# MB.net
KiCad netlist of a schematic drawn in Altium Designer
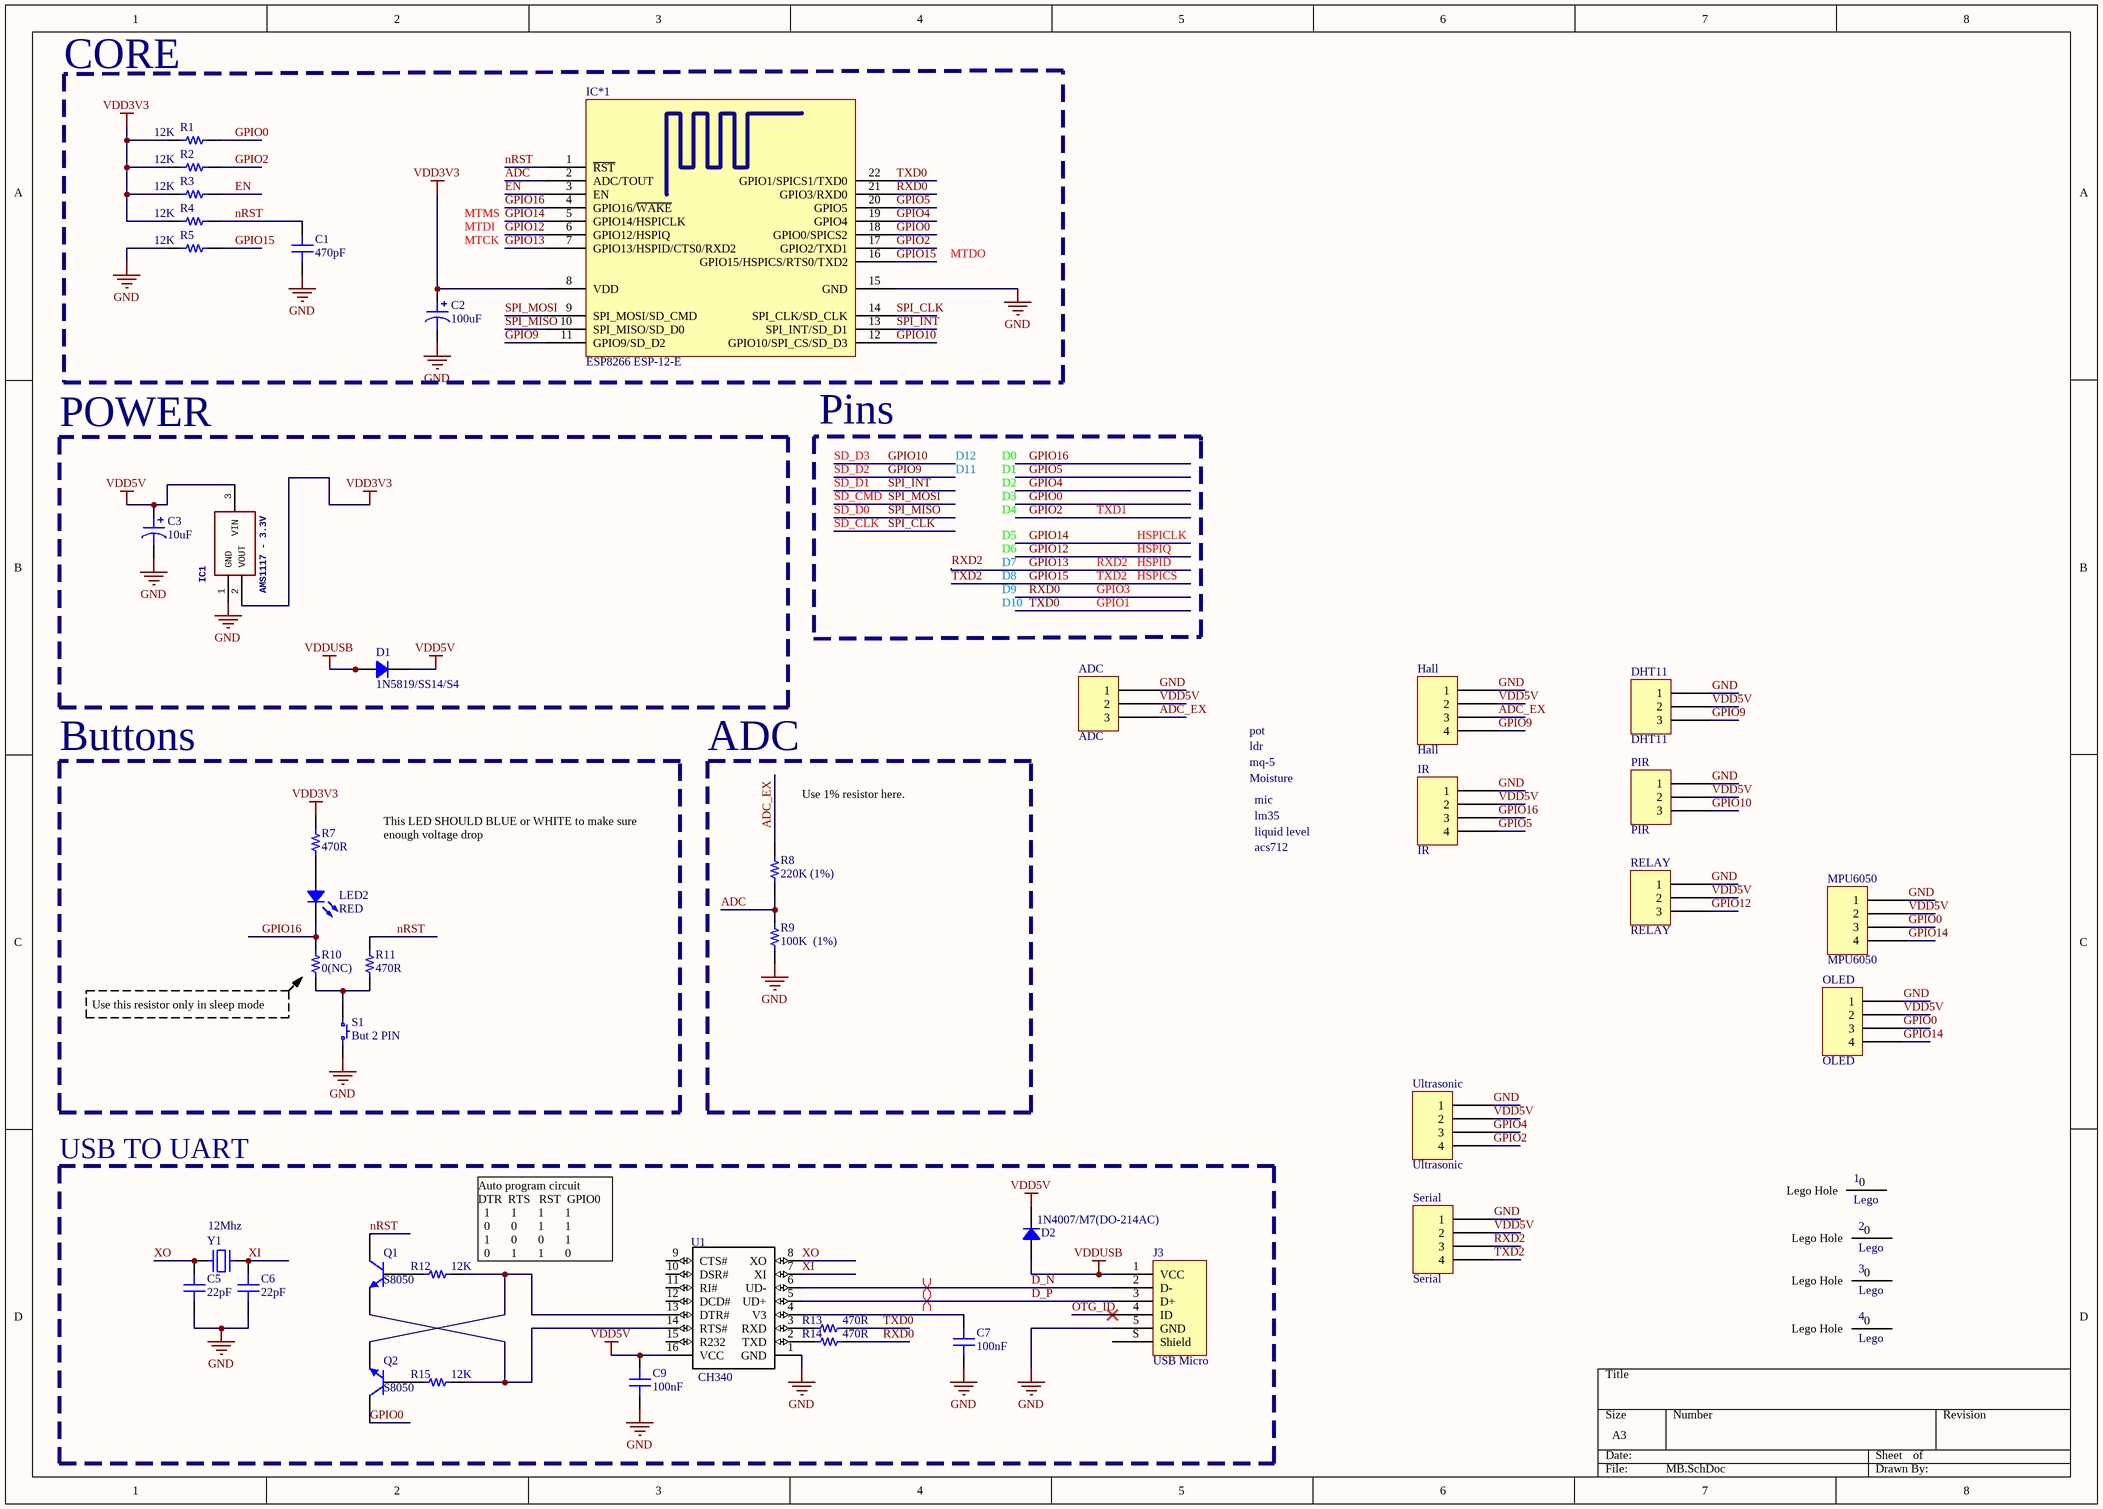
[diagram p0: MB.SchDoc]

(export (version "E")
  (design (tool "Eeschema 10.0.6"))
  (components
    (comp (ref "1") (value "Lego") (footprint "Lego Hole") (libsource (lib "Connectors") (part "Lego")))
    (comp (ref "2") (value "Lego") (footprint "Lego Hole") (libsource (lib "Connectors") (part "Lego")))
    (comp (ref "3") (value "Lego") (footprint "Lego Hole") (libsource (lib "Connectors") (part "Lego")))
    (comp (ref "4") (value "Lego") (footprint "Lego Hole") (libsource (lib "Connectors") (part "Lego")))
    (comp (ref "ADC")
      (value "ADC")
      (footprint "JST XH B3B-XH-A")
      (libsource (lib "Connectors") (part "3 Pin"))
    )
    (comp (ref "C1")
      (value "470pF")
      (footprint "CAP 1206/3216")
      (description "SMT Capacitor")
      (libsource (lib "Cap_Res") (part "Capacitor"))
    )
    (comp (ref "C2")
      (value "100uF")
      (footprint "CAP ALUM 5MM")
      (description "SMT Polarised Capacitor")
      (libsource (lib "Cap_Res") (part "Polarised Capacitor"))
    )
    (comp (ref "C3")
      (value "10uF")
      (footprint "CAP ALUM 5MM")
      (description "SMT Polarised Capacitor")
      (libsource (lib "Cap_Res") (part "Polarised Capacitor"))
    )
    (comp (ref "C5")
      (value "22pF")
      (footprint "CAP 1206/3216")
      (description "SMT Capacitor")
      (libsource (lib "Cap_Res") (part "Capacitor"))
    )
    (comp (ref "C6")
      (value "22pF")
      (footprint "CAP 1206/3216")
      (description "SMT Capacitor")
      (libsource (lib "Cap_Res") (part "Capacitor"))
    )
    (comp (ref "C7")
      (value "100nF")
      (footprint "CAP 1206/3216")
      (description "SMT Capacitor")
      (libsource (lib "Cap_Res") (part "Capacitor"))
    )
    (comp (ref "C9")
      (value "100nF")
      (footprint "CAP 1206/3216")
      (description "SMT Capacitor")
      (libsource (lib "Cap_Res") (part "Capacitor"))
    )
    (comp (ref "D1")
      (value "1N5819/SS14/S4")
      (footprint "DO214AC SMA")
      (description "Rectifier Diode")
      (libsource (lib "Cap_Res") (part "Diode"))
    )
    (comp (ref "D2")
      (value "1N4007/M7(DO-214AC)")
      (footprint "DO214AC SMA")
      (description "Rectifier Diode")
      (libsource (lib "Cap_Res") (part "Diode"))
    )
    (comp (ref "DHT11")
      (value "DHT11")
      (footprint "JST XH B3B-XH-A")
      (libsource (lib "Connectors") (part "3 Pin"))
    )
    (comp (ref "Hall")
      (value "Hall")
      (footprint "JST XH B4B-XH-A")
      (libsource (lib "Connectors") (part "4 Pin"))
    )
    (comp (ref "IC*1")
      (value "ESP8266 ESP-12-E")
      (footprint "ESP8266 ESP-12-E")
      (libsource (lib "ESP8266") (part "ESP8266 ESP-12-E"))
    )
    (comp (ref "IC1")
      (value "AMS1117 - 3.3V")
      (footprint "AMS1117")
      (fields (field (name "MANUFACTURER_PART_NUMBER") "ams1117-3.3v"))
      (libsource (lib "Other") (part "AMS1117"))
    )
    (comp (ref "IR") (value "IR") (footprint "JST XH B4B-XH-A") (libsource (lib "Connectors") (part "4 Pin")))
    (comp (ref "J3")
      (value "USB Micro")
      (footprint "FCI USB 10118193-0001LF")
      (libsource (lib "Connectors") (part "USB 2.0 Type B Micro"))
    )
    (comp (ref "LED2")
      (value "RED")
      (footprint "LED 1206/3216 BLUE")
      (description "Chip LED")
      (libsource (lib "Cap_Res") (part "LED"))
    )
    (comp (ref "MPU6050")
      (value "MPU6050")
      (footprint "JST XH B4B-XH-A")
      (libsource (lib "Connectors") (part "4 Pin"))
    )
    (comp (ref "OLED")
      (value "OLED")
      (footprint "JST XH B4B-XH-A")
      (libsource (lib "Connectors") (part "4 Pin"))
    )
    (comp (ref "PIR")
      (value "PIR")
      (footprint "JST XH B3B-XH-A")
      (libsource (lib "Connectors") (part "3 Pin"))
    )
    (comp (ref "Q1")
      (value "S8050")
      (footprint "SOT23")
      (description "NPN")
      (fields (field (name "E-MAIL") "picpars@gmail.com"))
      (libsource (lib "Other") (part "2N2222"))
    )
    (comp (ref "Q2")
      (value "S8050")
      (footprint "SOT23")
      (description "NPN")
      (fields (field (name "E-MAIL") "picpars@gmail.com"))
      (libsource (lib "Other") (part "2N2222"))
    )
    (comp (ref "R1")
      (value "12K")
      (footprint "RES 1206/3216")
      (description "SMT Resistor")
      (libsource (lib "Cap_Res") (part "Resistor"))
    )
    (comp (ref "R2")
      (value "12K")
      (footprint "RES 1206/3216")
      (description "SMT Resistor")
      (libsource (lib "Cap_Res") (part "Resistor"))
    )
    (comp (ref "R3")
      (value "12K")
      (footprint "RES 1206/3216")
      (description "SMT Resistor")
      (libsource (lib "Cap_Res") (part "Resistor"))
    )
    (comp (ref "R4")
      (value "12K")
      (footprint "RES 1206/3216")
      (description "SMT Resistor")
      (libsource (lib "Cap_Res") (part "Resistor"))
    )
    (comp (ref "R5")
      (value "12K")
      (footprint "RES 1206/3216")
      (description "SMT Resistor")
      (libsource (lib "Cap_Res") (part "Resistor"))
    )
    (comp (ref "R7")
      (value "470R")
      (footprint "RES 1206/3216")
      (description "SMT Resistor")
      (libsource (lib "Cap_Res") (part "Resistor"))
    )
    (comp (ref "R8")
      (value "220K (1%)")
      (footprint "RES 1206/3216")
      (description "SMT Resistor")
      (libsource (lib "Cap_Res") (part "Resistor"))
    )
    (comp (ref "R9")
      (value "100K  (1%)")
      (footprint "RES 1206/3216")
      (description "SMT Resistor")
      (libsource (lib "Cap_Res") (part "Resistor"))
    )
    (comp (ref "R10")
      (value "0(NC)")
      (footprint "RES 1206/3216")
      (description "SMT Resistor")
      (libsource (lib "Cap_Res") (part "Resistor"))
    )
    (comp (ref "R11")
      (value "470R")
      (footprint "RES 1206/3216")
      (description "SMT Resistor")
      (libsource (lib "Cap_Res") (part "Resistor"))
    )
    (comp (ref "R12")
      (value "12K")
      (footprint "RES 1206/3216")
      (description "SMT Resistor")
      (libsource (lib "Cap_Res") (part "Resistor"))
    )
    (comp (ref "R13")
      (value "470R")
      (footprint "RES 1206/3216")
      (description "SMT Resistor")
      (libsource (lib "Cap_Res") (part "Resistor"))
    )
    (comp (ref "R14")
      (value "470R")
      (footprint "RES 1206/3216")
      (description "SMT Resistor")
      (libsource (lib "Cap_Res") (part "Resistor"))
    )
    (comp (ref "R15")
      (value "12K")
      (footprint "RES 1206/3216")
      (description "SMT Resistor")
      (libsource (lib "Cap_Res") (part "Resistor"))
    )
    (comp (ref "RELAY")
      (value "RELAY")
      (footprint "JST XH B3B-XH-A")
      (libsource (lib "Connectors") (part "3 Pin"))
    )
    (comp (ref "S1")
      (value "But 2 PIN")
      (footprint "TE FSMSMTR")
      (libsource (lib "Other") (part "But 2 PIN"))
    )
    (comp (ref "Serial")
      (value "Serial")
      (footprint "JST XH B4B-XH-A")
      (libsource (lib "Connectors") (part "4 Pin"))
    )
    (comp (ref "U1")
      (value "CH340")
      (footprint "SO16")
      (fields (field (name "MF") "Eaton / Cutler Hammer"))
      (libsource (lib "Other") (part "CH340"))
    )
    (comp (ref "Ultrasonic")
      (value "Ultrasonic")
      (footprint "JST XH B4B-XH-A")
      (libsource (lib "Connectors") (part "4 Pin"))
    )
    (comp (ref "Y1")
      (value "12Mhz")
      (footprint "xtal")
      (description "SMT Crystal")
      (libsource (lib "Other") (part "xtal"))
    )
  )
  (nets
    (net (code "1") (name "/ADC") (class "Default")
      (node (ref "IC*1") (pin "2") (pinfunction "ADC/TOUT_2") (pintype "passive"))
      (node (ref "R8") (pin "2") (pinfunction "2_2") (pintype "passive"))
      (node (ref "R9") (pin "1") (pinfunction "1_1") (pintype "passive"))
    )
    (net (code "2") (name "/ADC_EX") (class "Default")
      (node (ref "ADC") (pin "3") (pinfunction "3_3") (pintype "passive"))
      (node (ref "Hall") (pin "3") (pinfunction "3_3") (pintype "passive"))
      (node (ref "R8") (pin "1") (pinfunction "1_1") (pintype "passive"))
    )
    (net (code "3") (name "/D_N") (class "Default")
      (node (ref "J3") (pin "2") (pinfunction "D-_2") (pintype "passive"))
      (node (ref "U1") (pin "6") (pinfunction "UD-_6") (pintype "bidirectional"))
    )
    (net (code "4") (name "/D_P") (class "Default")
      (node (ref "J3") (pin "3") (pinfunction "D+_3") (pintype "passive"))
      (node (ref "U1") (pin "5") (pinfunction "UD+_5") (pintype "bidirectional"))
    )
    (net (code "5") (name "/EN") (class "Default")
      (node (ref "IC*1") (pin "3") (pinfunction "EN_3") (pintype "passive"))
      (node (ref "R3") (pin "1") (pinfunction "1_1") (pintype "passive"))
    )
    (net (code "6") (name "/GPIO0") (class "Default")
      (node (ref "IC*1") (pin "18") (pinfunction "GPIO0/SPICS2_18") (pintype "passive"))
      (node (ref "MPU6050") (pin "3") (pinfunction "3_3") (pintype "passive"))
      (node (ref "OLED") (pin "3") (pinfunction "3_3") (pintype "passive"))
      (node (ref "Q2") (pin "C") (pinfunction "C_C") (pintype "passive"))
      (node (ref "R1") (pin "1") (pinfunction "1_1") (pintype "passive"))
    )
    (net (code "7") (name "/GPIO2") (class "Default")
      (node (ref "IC*1") (pin "17") (pinfunction "GPIO2/TXD1_17") (pintype "passive"))
      (node (ref "R2") (pin "1") (pinfunction "1_1") (pintype "passive"))
      (node (ref "Ultrasonic") (pin "4") (pinfunction "4_4") (pintype "passive"))
    )
    (net (code "8") (name "/GPIO4") (class "Default")
      (node (ref "IC*1") (pin "19") (pinfunction "GPIO4_19") (pintype "passive"))
      (node (ref "Ultrasonic") (pin "3") (pinfunction "3_3") (pintype "passive"))
    )
    (net (code "9") (name "/GPIO5") (class "Default")
      (node (ref "IC*1") (pin "20") (pinfunction "GPIO5_20") (pintype "passive"))
      (node (ref "IR") (pin "4") (pinfunction "4_4") (pintype "passive"))
    )
    (net (code "10") (name "/GPIO9") (class "Default")
      (node (ref "DHT11") (pin "3") (pinfunction "3_3") (pintype "passive"))
      (node (ref "Hall") (pin "4") (pinfunction "4_4") (pintype "passive"))
      (node (ref "IC*1") (pin "11") (pinfunction "GPIO9/SD_D2_11") (pintype "passive"))
    )
    (net (code "11") (name "/GPIO10") (class "Default")
      (node (ref "IC*1") (pin "12") (pinfunction "GPIO10/SPI_CS/SD_D3_12") (pintype "passive"))
      (node (ref "PIR") (pin "3") (pinfunction "3_3") (pintype "passive"))
    )
    (net (code "12") (name "/GPIO12") (class "Default")
      (node (ref "IC*1") (pin "6") (pinfunction "GPIO12/HSPIQ_6") (pintype "passive"))
      (node (ref "RELAY") (pin "3") (pinfunction "3_3") (pintype "passive"))
    )
    (net (code "13") (name "/GPIO13") (class "Default")
      (node (ref "IC*1") (pin "7") (pinfunction "GPIO13/HSPID/CTS0/RXD2_7") (pintype "passive"))
      (node (ref "Serial") (pin "3") (pinfunction "3_3") (pintype "passive"))
    )
    (net (code "14") (name "/GPIO14") (class "Default")
      (node (ref "IC*1") (pin "5") (pinfunction "GPIO14/HSPICLK_5") (pintype "passive"))
      (node (ref "MPU6050") (pin "4") (pinfunction "4_4") (pintype "passive"))
      (node (ref "OLED") (pin "4") (pinfunction "4_4") (pintype "passive"))
    )
    (net (code "15") (name "/GPIO15") (class "Default")
      (node (ref "IC*1") (pin "16") (pinfunction "GPIO15/HSPICS/RTS0/TXD2_16") (pintype "passive"))
      (node (ref "R5") (pin "1") (pinfunction "1_1") (pintype "passive"))
      (node (ref "Serial") (pin "4") (pinfunction "4_4") (pintype "passive"))
    )
    (net (code "16") (name "/GPIO16") (class "Default")
      (node (ref "IC*1") (pin "4") (pinfunction "GPIO16/~{WAKE}_4") (pintype "passive"))
      (node (ref "IR") (pin "3") (pinfunction "3_3") (pintype "passive"))
      (node (ref "LED2") (pin "2") (pinfunction "2_2") (pintype "passive"))
      (node (ref "R10") (pin "1") (pinfunction "1_1") (pintype "passive"))
    )
    (net (code "17") (name "/OTG_ID") (class "Default")
      (node (ref "J3") (pin "4") (pinfunction "ID_4") (pintype "passive+no_connect"))
    )
    (net (code "18") (name "/RXD0") (class "Default")
      (node (ref "IC*1") (pin "21") (pinfunction "GPIO3/RXD0_21") (pintype "passive"))
      (node (ref "R14") (pin "2") (pinfunction "2_2") (pintype "passive"))
    )
    (net (code "19") (name "/SPI_CLK") (class "Default")
      (node (ref "IC*1") (pin "14") (pinfunction "SPI_CLK/SD_CLK_14") (pintype "passive"))
    )
    (net (code "20") (name "/SPI_INT") (class "Default")
      (node (ref "IC*1") (pin "13") (pinfunction "SPI_INT/SD_D1_13") (pintype "passive"))
    )
    (net (code "21") (name "/SPI_MISO") (class "Default")
      (node (ref "IC*1") (pin "10") (pinfunction "SPI_MISO/SD_D0_10") (pintype "passive"))
    )
    (net (code "22") (name "/SPI_MOSI") (class "Default")
      (node (ref "IC*1") (pin "9") (pinfunction "SPI_MOSI/SD_CMD_9") (pintype "passive"))
    )
    (net (code "23") (name "/TXD0") (class "Default")
      (node (ref "IC*1") (pin "22") (pinfunction "GPIO1/SPICS1/TXD0_22") (pintype "passive"))
      (node (ref "R13") (pin "2") (pinfunction "2_2") (pintype "passive"))
    )
    (net (code "24") (name "/XI") (class "Default")
      (node (ref "C6") (pin "2") (pinfunction "2_2") (pintype "passive"))
      (node (ref "U1") (pin "7") (pinfunction "XI_7") (pintype "bidirectional"))
      (node (ref "Y1") (pin "2") (pinfunction "2_2") (pintype "passive"))
    )
    (net (code "25") (name "/XO") (class "Default")
      (node (ref "C5") (pin "2") (pinfunction "2_2") (pintype "passive"))
      (node (ref "U1") (pin "8") (pinfunction "XO_8") (pintype "bidirectional"))
      (node (ref "Y1") (pin "1") (pinfunction "1_1") (pintype "passive"))
    )
    (net (code "26") (name "/nRST") (class "Default")
      (node (ref "C1") (pin "2") (pinfunction "2_2") (pintype "passive"))
      (node (ref "IC*1") (pin "1") (pinfunction "~{RST}_1") (pintype "passive"))
      (node (ref "Q1") (pin "C") (pinfunction "C_C") (pintype "passive"))
      (node (ref "R11") (pin "1") (pinfunction "1_1") (pintype "passive"))
      (node (ref "R4") (pin "1") (pinfunction "1_1") (pintype "passive"))
    )
    (net (code "27") (name "GND") (class "Default")
      (node (ref "ADC") (pin "1") (pinfunction "1_1") (pintype "passive"))
      (node (ref "C1") (pin "1") (pinfunction "1_1") (pintype "passive"))
      (node (ref "C2") (pin "2") (pinfunction "2_2") (pintype "passive"))
      (node (ref "C3") (pin "2") (pinfunction "2_2") (pintype "passive"))
      (node (ref "C5") (pin "1") (pinfunction "1_1") (pintype "passive"))
      (node (ref "C6") (pin "1") (pinfunction "1_1") (pintype "passive"))
      (node (ref "C7") (pin "1") (pinfunction "1_1") (pintype "passive"))
      (node (ref "C9") (pin "1") (pinfunction "1_1") (pintype "passive"))
      (node (ref "DHT11") (pin "1") (pinfunction "1_1") (pintype "passive"))
      (node (ref "Hall") (pin "1") (pinfunction "1_1") (pintype "passive"))
      (node (ref "IC*1") (pin "15") (pinfunction "GND_15") (pintype "passive"))
      (node (ref "IC1") (pin "1") (pinfunction "GND_1") (pintype "passive"))
      (node (ref "IR") (pin "1") (pinfunction "1_1") (pintype "passive"))
      (node (ref "J3") (pin "5") (pinfunction "GND_5") (pintype "passive"))
      (node (ref "MPU6050") (pin "1") (pinfunction "1_1") (pintype "passive"))
      (node (ref "OLED") (pin "1") (pinfunction "1_1") (pintype "passive"))
      (node (ref "PIR") (pin "1") (pinfunction "1_1") (pintype "passive"))
      (node (ref "R5") (pin "2") (pinfunction "2_2") (pintype "passive"))
      (node (ref "R9") (pin "2") (pinfunction "2_2") (pintype "passive"))
      (node (ref "RELAY") (pin "1") (pinfunction "1_1") (pintype "passive"))
      (node (ref "S1") (pin "2") (pinfunction "2_2") (pintype "passive"))
      (node (ref "Serial") (pin "1") (pinfunction "1_1") (pintype "passive"))
      (node (ref "U1") (pin "1") (pinfunction "GND_1") (pintype "power_in"))
      (node (ref "Ultrasonic") (pin "1") (pinfunction "1_1") (pintype "passive"))
    )
    (net (code "28") (name "Net-(LED2-Pad1)") (class "Default")
      (node (ref "LED2") (pin "1") (pinfunction "1_1") (pintype "passive"))
      (node (ref "R7") (pin "2") (pinfunction "2_2") (pintype "passive"))
    )
    (net (code "29") (name "Net-(Q1-PadB)") (class "Default")
      (node (ref "Q1") (pin "B") (pinfunction "B_B") (pintype "passive"))
      (node (ref "R12") (pin "1") (pinfunction "1_1") (pintype "passive"))
    )
    (net (code "30") (name "Net-(Q2-PadB)") (class "Default")
      (node (ref "Q2") (pin "B") (pinfunction "B_B") (pintype "passive"))
      (node (ref "R15") (pin "1") (pinfunction "1_1") (pintype "passive"))
    )
    (net (code "31") (name "Net-(R10-Pad2)") (class "Default")
      (node (ref "R10") (pin "2") (pinfunction "2_2") (pintype "passive"))
      (node (ref "R11") (pin "2") (pinfunction "2_2") (pintype "passive"))
      (node (ref "S1") (pin "1") (pinfunction "1_1") (pintype "passive"))
    )
    (net (code "32") (name "Net-(U1-DTR#)") (class "Default")
      (node (ref "Q2") (pin "E") (pinfunction "E_E") (pintype "passive"))
      (node (ref "R12") (pin "2") (pinfunction "2_2") (pintype "passive"))
      (node (ref "U1") (pin "13") (pinfunction "DTR#_13") (pintype "bidirectional"))
    )
    (net (code "33") (name "Net-(U1-RTS#)") (class "Default")
      (node (ref "Q1") (pin "E") (pinfunction "E_E") (pintype "passive"))
      (node (ref "R15") (pin "2") (pinfunction "2_2") (pintype "passive"))
      (node (ref "U1") (pin "14") (pinfunction "RTS#_14") (pintype "bidirectional"))
    )
    (net (code "34") (name "Net-(U1-RXD)") (class "Default")
      (node (ref "R13") (pin "1") (pinfunction "1_1") (pintype "passive"))
      (node (ref "U1") (pin "3") (pinfunction "RXD_3") (pintype "bidirectional"))
    )
    (net (code "35") (name "Net-(U1-TXD)") (class "Default")
      (node (ref "R14") (pin "1") (pinfunction "1_1") (pintype "passive"))
      (node (ref "U1") (pin "2") (pinfunction "TXD_2") (pintype "bidirectional"))
    )
    (net (code "36") (name "Net-(U1-V3)") (class "Default")
      (node (ref "C7") (pin "2") (pinfunction "2_2") (pintype "passive"))
      (node (ref "U1") (pin "4") (pinfunction "V3_4") (pintype "bidirectional"))
    )
    (net (code "37") (name "VDD3V3") (class "Default")
      (node (ref "C2") (pin "1") (pinfunction "1_1") (pintype "passive"))
      (node (ref "IC*1") (pin "8") (pinfunction "VDD_8") (pintype "passive"))
      (node (ref "IC1") (pin "2") (pinfunction "VOUT_2") (pintype "passive"))
      (node (ref "R1") (pin "2") (pinfunction "2_2") (pintype "passive"))
      (node (ref "R2") (pin "2") (pinfunction "2_2") (pintype "passive"))
      (node (ref "R3") (pin "2") (pinfunction "2_2") (pintype "passive"))
      (node (ref "R4") (pin "2") (pinfunction "2_2") (pintype "passive"))
      (node (ref "R7") (pin "1") (pinfunction "1_1") (pintype "passive"))
    )
    (net (code "38") (name "VDD5V") (class "Default")
      (node (ref "ADC") (pin "2") (pinfunction "2_2") (pintype "passive"))
      (node (ref "C3") (pin "1") (pinfunction "1_1") (pintype "passive"))
      (node (ref "C9") (pin "2") (pinfunction "2_2") (pintype "passive"))
      (node (ref "D1") (pin "2") (pinfunction "2_2") (pintype "passive"))
      (node (ref "D2") (pin "2") (pinfunction "2_2") (pintype "passive"))
      (node (ref "DHT11") (pin "2") (pinfunction "2_2") (pintype "passive"))
      (node (ref "Hall") (pin "2") (pinfunction "2_2") (pintype "passive"))
      (node (ref "IC1") (pin "3") (pinfunction "VIN_3") (pintype "passive"))
      (node (ref "IR") (pin "2") (pinfunction "2_2") (pintype "passive"))
      (node (ref "MPU6050") (pin "2") (pinfunction "2_2") (pintype "passive"))
      (node (ref "OLED") (pin "2") (pinfunction "2_2") (pintype "passive"))
      (node (ref "PIR") (pin "2") (pinfunction "2_2") (pintype "passive"))
      (node (ref "RELAY") (pin "2") (pinfunction "2_2") (pintype "passive"))
      (node (ref "Serial") (pin "2") (pinfunction "2_2") (pintype "passive"))
      (node (ref "U1") (pin "16") (pinfunction "VCC_16") (pintype "power_in"))
      (node (ref "Ultrasonic") (pin "2") (pinfunction "2_2") (pintype "passive"))
    )
    (net (code "39") (name "VDDUSB") (class "Default")
      (node (ref "D1") (pin "1") (pinfunction "1_1") (pintype "passive"))
      (node (ref "D2") (pin "1") (pinfunction "1_1") (pintype "passive"))
      (node (ref "J3") (pin "1") (pinfunction "VCC_1") (pintype "passive"))
    )
    (net (code "40") (name "unconnected-(1-Lego_Hole-Pad0)") (class "Default")
      (node (ref "1") (pin "0") (pinfunction "Lego_Hole_0") (pintype "passive"))
    )
    (net (code "41") (name "unconnected-(2-Lego_Hole-Pad0)") (class "Default")
      (node (ref "2") (pin "0") (pinfunction "Lego_Hole_0") (pintype "passive"))
    )
    (net (code "42") (name "unconnected-(3-Lego_Hole-Pad0)") (class "Default")
      (node (ref "3") (pin "0") (pinfunction "Lego_Hole_0") (pintype "passive"))
    )
    (net (code "43") (name "unconnected-(4-Lego_Hole-Pad0)") (class "Default")
      (node (ref "4") (pin "0") (pinfunction "Lego_Hole_0") (pintype "passive"))
    )
    (net (code "44") (name "unconnected-(J3-Shield-PadS)") (class "Default")
      (node (ref "J3") (pin "S") (pinfunction "Shield_S") (pintype "passive"))
    )
    (net (code "45") (name "unconnected-(U1-CTS#-Pad9)") (class "Default")
      (node (ref "U1") (pin "9") (pinfunction "CTS#_9") (pintype "bidirectional"))
    )
    (net (code "46") (name "unconnected-(U1-DCD#-Pad12)") (class "Default")
      (node (ref "U1") (pin "12") (pinfunction "DCD#_12") (pintype "bidirectional"))
    )
    (net (code "47") (name "unconnected-(U1-DSR#-Pad10)") (class "Default")
      (node (ref "U1") (pin "10") (pinfunction "DSR#_10") (pintype "bidirectional"))
    )
    (net (code "48") (name "unconnected-(U1-R232-Pad15)") (class "Default")
      (node (ref "U1") (pin "15") (pinfunction "R232_15") (pintype "bidirectional"))
    )
    (net (code "49") (name "unconnected-(U1-RI#-Pad11)") (class "Default")
      (node (ref "U1") (pin "11") (pinfunction "RI#_11") (pintype "bidirectional"))
    )
  )
)
